# Communication.net
KiCad netlist of a schematic drawn in Altium Designer
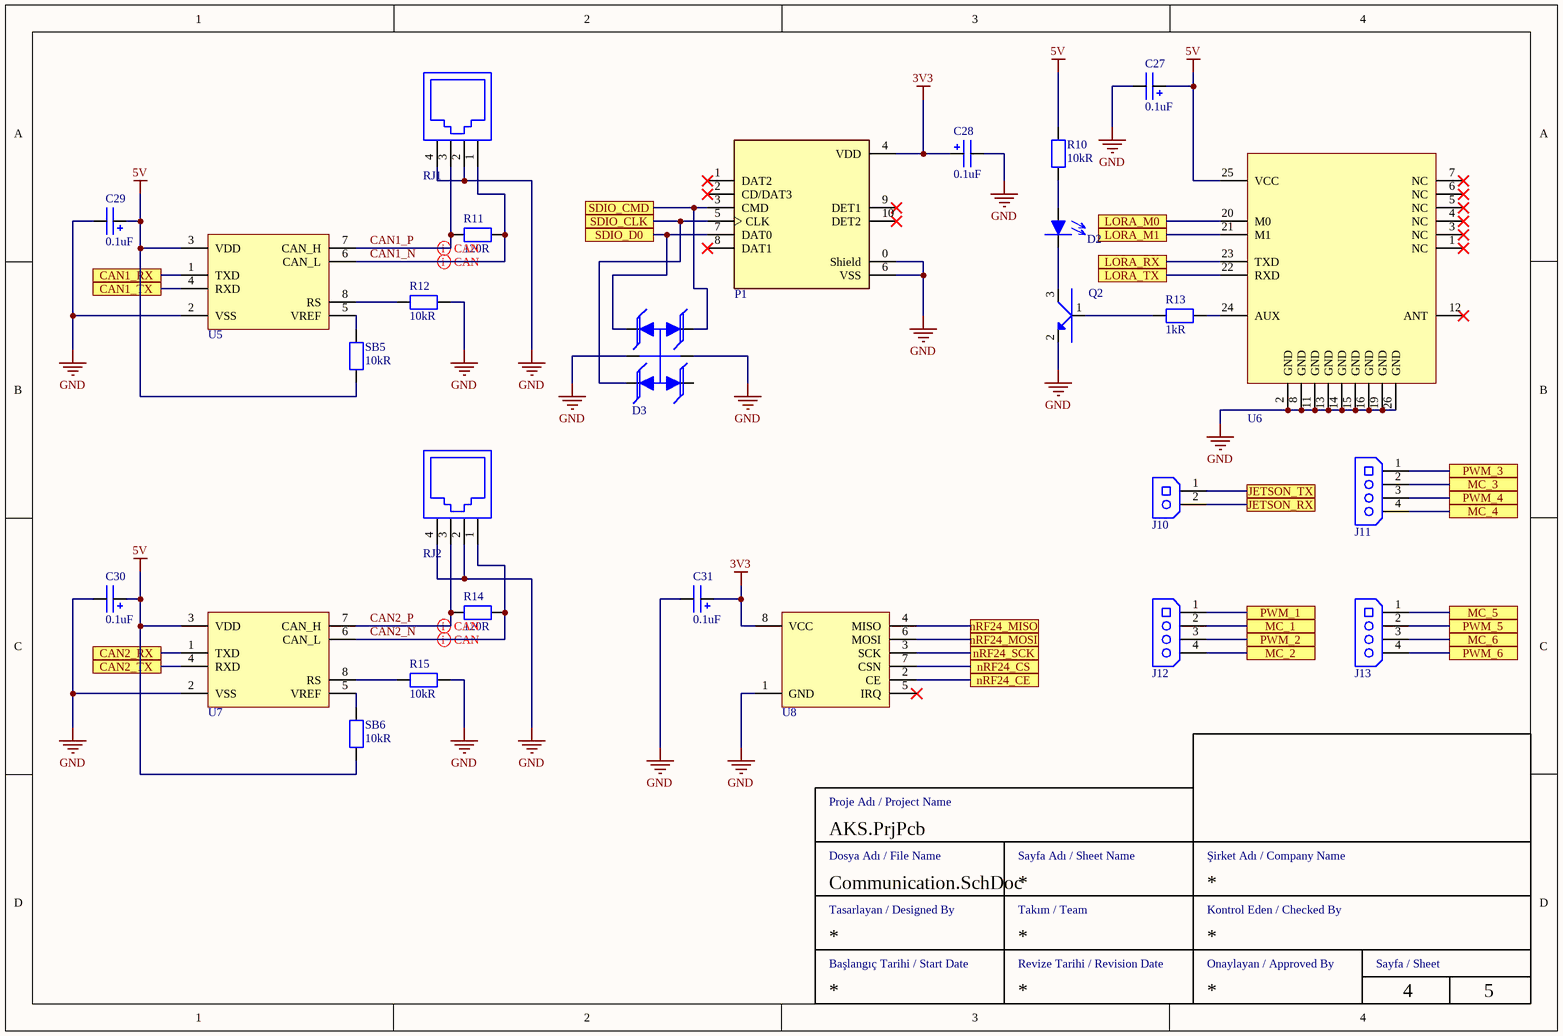
[diagram p0: Communication.SchDoc]

(export (version "E")
  (design (tool "Eeschema 10.0.6"))
  (components
    (comp (ref "C27")
      (value "0.1uF")
      (footprint "CAP 0603")
      (description "Multilayer Ceramic Capacitor")
      (fields (field (name "Comment") "CAP 0603"))
      (libsource (lib "Kaptanyums Lib") (part "CAP 0603"))
    )
    (comp (ref "C28")
      (value "0.1uF")
      (footprint "CAP 0603")
      (description "Multilayer Ceramic Capacitor")
      (fields (field (name "Comment") "CAP 0603"))
      (libsource (lib "Kaptanyums Lib") (part "CAP 0603"))
    )
    (comp (ref "C29")
      (value "0.1uF")
      (footprint "CAP 0603")
      (description "Multilayer Ceramic Capacitor")
      (fields (field (name "Comment") "CAP 0603"))
      (libsource (lib "Kaptanyums Lib") (part "CAP 0603"))
    )
    (comp (ref "C30")
      (value "0.1uF")
      (footprint "CAP 0603")
      (description "Multilayer Ceramic Capacitor")
      (fields (field (name "Comment") "CAP 0603"))
      (libsource (lib "Kaptanyums Lib") (part "CAP 0603"))
    )
    (comp (ref "C31")
      (value "0.1uF")
      (footprint "CAP 0603")
      (description "Multilayer Ceramic Capacitor")
      (fields (field (name "Comment") "CAP 0603"))
      (libsource (lib "Kaptanyums Lib") (part "CAP 0603"))
    )
    (comp (ref "D2")
      (value "LTW-C191TLA")
      (footprint "LED 0603")
      (description "Chip LED")
      (libsource (lib "Kaptanyums Lib") (part "LED 0603"))
    )
    (comp (ref "D3")
      (value "ESDA6V1SC6")
      (footprint "SOT23-6")
      (description "Diode TVS Array")
      (fields (field (name "VOLTAGE") "5.25V"))
      (libsource (lib "Kaptanyums Lib") (part "ESDA6V1SC6"))
    )
    (comp (ref "J10")
      (value "JSTXH2")
      (footprint "JSTXH2")
      (description "JST Socket for PCB")
      (libsource (lib "Kaptanyums Lib") (part "JSTXH2"))
    )
    (comp (ref "J11")
      (value "JSTXH4")
      (footprint "JSTXH4")
      (description "JST Socket for PCB")
      (libsource (lib "Kaptanyums Lib") (part "JSTXH4"))
    )
    (comp (ref "J12")
      (value "JSTXH4")
      (footprint "JSTXH4")
      (description "JST Socket for PCB")
      (libsource (lib "Kaptanyums Lib") (part "JSTXH4"))
    )
    (comp (ref "J13")
      (value "JSTXH4")
      (footprint "JSTXH4")
      (description "JST Socket for PCB")
      (libsource (lib "Kaptanyums Lib") (part "JSTXH4"))
    )
    (comp (ref "P1")
      (value "DM3AT-SF-PEJM5")
      (footprint "SD CARD (8+2)")
      (description "Micro SD Card Adapter")
      (libsource (lib "Kaptanyums Lib") (part "DM3AT-SF-PEJM5"))
    )
    (comp (ref "Q2")
      (value "BC817-40")
      (footprint "SOT23-3")
      (description "Transistor BJT")
      (fields (field (name "VOLTAGE") "45V"))
      (libsource (lib "Kaptanyums Lib") (part "BC817-40"))
    )
    (comp (ref "R10")
      (value "10kR")
      (footprint "RESISTOR 0603")
      (description "SMD Chip Resistor")
      (fields (field (name "Comment") "RES 0603"))
      (libsource (lib "Kaptanyums Lib") (part "RES 0603"))
    )
    (comp (ref "R11")
      (value "120R")
      (footprint "RESISTOR 0603")
      (description "SMD Chip Resistor")
      (fields (field (name "Comment") "RES 0603"))
      (libsource (lib "Kaptanyums Lib") (part "RES 0603"))
    )
    (comp (ref "R12")
      (value "10kR")
      (footprint "RESISTOR 0603")
      (description "SMD Chip Resistor")
      (fields (field (name "Comment") "RES 0603"))
      (libsource (lib "Kaptanyums Lib") (part "RES 0603"))
    )
    (comp (ref "R13")
      (value "1kR")
      (footprint "RESISTOR 0603")
      (description "SMD Chip Resistor")
      (fields (field (name "Comment") "RES 0603"))
      (libsource (lib "Kaptanyums Lib") (part "RES 0603"))
    )
    (comp (ref "R14")
      (value "120R")
      (footprint "RESISTOR 0603")
      (description "SMD Chip Resistor")
      (fields (field (name "Comment") "RES 0603"))
      (libsource (lib "Kaptanyums Lib") (part "RES 0603"))
    )
    (comp (ref "R15")
      (value "10kR")
      (footprint "RESISTOR 0603")
      (description "SMD Chip Resistor")
      (fields (field (name "Comment") "RES 0603"))
      (libsource (lib "Kaptanyums Lib") (part "RES 0603"))
    )
    (comp (ref "RJ1")
      (value "DS1133-03-S60BX")
      (footprint "RJ6P4C")
      (description "RJ11 Jack")
      (libsource (lib "Kaptanyums Lib") (part "RJ11"))
    )
    (comp (ref "RJ2")
      (value "DS1133-03-S60BX")
      (footprint "RJ6P4C")
      (description "RJ11 Jack")
      (libsource (lib "Kaptanyums Lib") (part "RJ11"))
    )
    (comp (ref "SB5")
      (value "10kR")
      (footprint "RESISTOR 0603")
      (description "SMD Chip Resistor")
      (fields (field (name "Comment") "RES 0603"))
      (libsource (lib "Kaptanyums Lib") (part "RES 0603"))
    )
    (comp (ref "SB6")
      (value "10kR")
      (footprint "RESISTOR 0603")
      (description "SMD Chip Resistor")
      (fields (field (name "Comment") "RES 0603"))
      (libsource (lib "Kaptanyums Lib") (part "RES 0603"))
    )
    (comp (ref "U5")
      (value "MCP2551T-I")
      (footprint "SOIC-8")
      (description "CAN Transceiver")
      (libsource (lib "Kaptanyums Lib") (part "MCP2551T-I"))
    )
    (comp (ref "U6")
      (value "E220-400")
      (footprint "E220-400T22S")
      (description "RF Transceiver")
      (libsource (lib "Kaptanyums Lib") (part "E220-400"))
    )
    (comp (ref "U7")
      (value "MCP2551T-I")
      (footprint "SOIC-8")
      (description "CAN Transceiver")
      (libsource (lib "Kaptanyums Lib") (part "MCP2551T-I"))
    )
    (comp (ref "U8")
      (value "NRF24")
      (footprint "nRF24L01+")
      (description "RF Transceiver")
      (libsource (lib "Kaptanyums Lib") (part "NRF24"))
    )
  )
  (nets
    (net (code "1") (name "/CAN1_N") (class "Default")
      (node (ref "R11") (pin "1") (pinfunction "1_1") (pintype "passive"))
      (node (ref "RJ1") (pin "1") (pinfunction "1_1") (pintype "passive"))
      (node (ref "U5") (pin "6") (pinfunction "CAN_L_6") (pintype "passive"))
    )
    (net (code "2") (name "/CAN1_P") (class "Default")
      (node (ref "R11") (pin "2") (pinfunction "2_2") (pintype "passive"))
      (node (ref "RJ1") (pin "3") (pinfunction "3_3") (pintype "passive"))
      (node (ref "U5") (pin "7") (pinfunction "CAN_H_7") (pintype "passive"))
    )
    (net (code "3") (name "/CAN1_RX") (class "Default")
      (node (ref "U5") (pin "1") (pinfunction "TXD_1") (pintype "passive"))
    )
    (net (code "4") (name "/CAN1_TX") (class "Default")
      (node (ref "U5") (pin "4") (pinfunction "RXD_4") (pintype "passive"))
    )
    (net (code "5") (name "/CAN2_N") (class "Default")
      (node (ref "R14") (pin "1") (pinfunction "1_1") (pintype "passive"))
      (node (ref "RJ2") (pin "1") (pinfunction "1_1") (pintype "passive"))
      (node (ref "U7") (pin "6") (pinfunction "CAN_L_6") (pintype "passive"))
    )
    (net (code "6") (name "/CAN2_P") (class "Default")
      (node (ref "R14") (pin "2") (pinfunction "2_2") (pintype "passive"))
      (node (ref "RJ2") (pin "3") (pinfunction "3_3") (pintype "passive"))
      (node (ref "U7") (pin "7") (pinfunction "CAN_H_7") (pintype "passive"))
    )
    (net (code "7") (name "/CAN2_RX") (class "Default")
      (node (ref "U7") (pin "1") (pinfunction "TXD_1") (pintype "passive"))
    )
    (net (code "8") (name "/CAN2_TX") (class "Default")
      (node (ref "U7") (pin "4") (pinfunction "RXD_4") (pintype "passive"))
    )
    (net (code "9") (name "/JETSON_RX") (class "Default")
      (node (ref "J10") (pin "2") (pinfunction "2_2") (pintype "passive"))
    )
    (net (code "10") (name "/JETSON_TX") (class "Default")
      (node (ref "J10") (pin "1") (pinfunction "1_1") (pintype "passive"))
    )
    (net (code "11") (name "/LORA_M0") (class "Default")
      (node (ref "U6") (pin "20") (pinfunction "M0_20") (pintype "passive"))
    )
    (net (code "12") (name "/LORA_M1") (class "Default")
      (node (ref "U6") (pin "21") (pinfunction "M1_21") (pintype "passive"))
    )
    (net (code "13") (name "/LORA_RX") (class "Default")
      (node (ref "U6") (pin "23") (pinfunction "TXD_23") (pintype "passive"))
    )
    (net (code "14") (name "/LORA_TX") (class "Default")
      (node (ref "U6") (pin "22") (pinfunction "RXD_22") (pintype "passive"))
    )
    (net (code "15") (name "/MC_1") (class "Default")
      (node (ref "J12") (pin "2") (pinfunction "2_2") (pintype "passive"))
    )
    (net (code "16") (name "/MC_2") (class "Default")
      (node (ref "J12") (pin "4") (pinfunction "4_4") (pintype "passive"))
    )
    (net (code "17") (name "/MC_3") (class "Default")
      (node (ref "J11") (pin "2") (pinfunction "2_2") (pintype "passive"))
    )
    (net (code "18") (name "/MC_4") (class "Default")
      (node (ref "J11") (pin "4") (pinfunction "4_4") (pintype "passive"))
    )
    (net (code "19") (name "/MC_5") (class "Default")
      (node (ref "J13") (pin "1") (pinfunction "1_1") (pintype "passive"))
    )
    (net (code "20") (name "/MC_6") (class "Default")
      (node (ref "J13") (pin "3") (pinfunction "3_3") (pintype "passive"))
    )
    (net (code "21") (name "/PWM_1") (class "Default")
      (node (ref "J12") (pin "1") (pinfunction "1_1") (pintype "passive"))
    )
    (net (code "22") (name "/PWM_2") (class "Default")
      (node (ref "J12") (pin "3") (pinfunction "3_3") (pintype "passive"))
    )
    (net (code "23") (name "/PWM_3") (class "Default")
      (node (ref "J11") (pin "1") (pinfunction "1_1") (pintype "passive"))
    )
    (net (code "24") (name "/PWM_4") (class "Default")
      (node (ref "J11") (pin "3") (pinfunction "3_3") (pintype "passive"))
    )
    (net (code "25") (name "/PWM_5") (class "Default")
      (node (ref "J13") (pin "2") (pinfunction "2_2") (pintype "passive"))
    )
    (net (code "26") (name "/PWM_6") (class "Default")
      (node (ref "J13") (pin "4") (pinfunction "4_4") (pintype "passive"))
    )
    (net (code "27") (name "/SDIO_CLK") (class "Default")
      (node (ref "D3") (pin "6") (pinfunction "6_6") (pintype "passive"))
      (node (ref "P1") (pin "5") (pinfunction "CLK_5") (pintype "passive"))
    )
    (net (code "28") (name "/SDIO_CMD") (class "Default")
      (node (ref "D3") (pin "3") (pinfunction "3_3") (pintype "passive"))
      (node (ref "P1") (pin "3") (pinfunction "CMD_3") (pintype "passive"))
    )
    (net (code "29") (name "/SDIO_D0") (class "Default")
      (node (ref "D3") (pin "4") (pinfunction "4_4") (pintype "passive"))
      (node (ref "P1") (pin "7") (pinfunction "DAT0_7") (pintype "passive"))
    )
    (net (code "30") (name "/nRF24_CE") (class "Default")
      (node (ref "U8") (pin "2") (pinfunction "CE_2") (pintype "passive"))
    )
    (net (code "31") (name "/nRF24_CS") (class "Default")
      (node (ref "U8") (pin "7") (pinfunction "CSN_7") (pintype "passive"))
    )
    (net (code "32") (name "/nRF24_MISO") (class "Default")
      (node (ref "U8") (pin "4") (pinfunction "MISO_4") (pintype "passive"))
    )
    (net (code "33") (name "/nRF24_MOSI") (class "Default")
      (node (ref "U8") (pin "6") (pinfunction "MOSI_6") (pintype "passive"))
    )
    (net (code "34") (name "/nRF24_SCK") (class "Default")
      (node (ref "U8") (pin "3") (pinfunction "SCK_3") (pintype "passive"))
    )
    (net (code "35") (name "3V3") (class "Default")
      (node (ref "C28") (pin "1") (pinfunction "1_1") (pintype "passive"))
      (node (ref "C31") (pin "1") (pinfunction "1_1") (pintype "passive"))
      (node (ref "P1") (pin "4") (pinfunction "VDD_4") (pintype "power_in"))
      (node (ref "U8") (pin "8") (pinfunction "VCC_8") (pintype "passive"))
    )
    (net (code "36") (name "5V") (class "Default")
      (node (ref "C27") (pin "1") (pinfunction "1_1") (pintype "passive"))
      (node (ref "C29") (pin "1") (pinfunction "1_1") (pintype "passive"))
      (node (ref "C30") (pin "1") (pinfunction "1_1") (pintype "passive"))
      (node (ref "R10") (pin "2") (pinfunction "2_2") (pintype "passive"))
      (node (ref "SB5") (pin "1") (pinfunction "1_1") (pintype "passive"))
      (node (ref "SB6") (pin "1") (pinfunction "1_1") (pintype "passive"))
      (node (ref "U5") (pin "3") (pinfunction "VDD_3") (pintype "passive"))
      (node (ref "U6") (pin "25") (pinfunction "VCC_25") (pintype "passive"))
      (node (ref "U7") (pin "3") (pinfunction "VDD_3") (pintype "passive"))
    )
    (net (code "37") (name "GND") (class "Default")
      (node (ref "C27") (pin "2") (pinfunction "2_2") (pintype "passive"))
      (node (ref "C28") (pin "2") (pinfunction "2_2") (pintype "passive"))
      (node (ref "C29") (pin "2") (pinfunction "2_2") (pintype "passive"))
      (node (ref "C30") (pin "2") (pinfunction "2_2") (pintype "passive"))
      (node (ref "C31") (pin "2") (pinfunction "2_2") (pintype "passive"))
      (node (ref "D3") (pin "2") (pinfunction "2_2") (pintype "passive"))
      (node (ref "D3") (pin "5") (pinfunction "5_5") (pintype "passive"))
      (node (ref "P1") (pin "0") (pinfunction "Shield_0") (pintype "passive"))
      (node (ref "P1") (pin "6") (pinfunction "VSS_6") (pintype "power_in"))
      (node (ref "Q2") (pin "2") (pinfunction "S_2") (pintype "passive"))
      (node (ref "R12") (pin "2") (pinfunction "2_2") (pintype "passive"))
      (node (ref "R15") (pin "2") (pinfunction "2_2") (pintype "passive"))
      (node (ref "RJ1") (pin "2") (pinfunction "2_2") (pintype "passive"))
      (node (ref "RJ1") (pin "4") (pinfunction "4_4") (pintype "passive"))
      (node (ref "RJ2") (pin "2") (pinfunction "2_2") (pintype "passive"))
      (node (ref "RJ2") (pin "4") (pinfunction "4_4") (pintype "passive"))
      (node (ref "U5") (pin "2") (pinfunction "VSS_2") (pintype "passive"))
      (node (ref "U6") (pin "11") (pinfunction "GND_11") (pintype "passive"))
      (node (ref "U6") (pin "13") (pinfunction "GND_13") (pintype "passive"))
      (node (ref "U6") (pin "14") (pinfunction "GND_14") (pintype "passive"))
      (node (ref "U6") (pin "15") (pinfunction "GND_15") (pintype "passive"))
      (node (ref "U6") (pin "16") (pinfunction "GND_16") (pintype "passive"))
      (node (ref "U6") (pin "19") (pinfunction "GND_19") (pintype "passive"))
      (node (ref "U6") (pin "2") (pinfunction "GND_2") (pintype "passive"))
      (node (ref "U6") (pin "26") (pinfunction "GND_26") (pintype "passive"))
      (node (ref "U6") (pin "8") (pinfunction "GND_8") (pintype "passive"))
      (node (ref "U7") (pin "2") (pinfunction "VSS_2") (pintype "passive"))
      (node (ref "U8") (pin "1") (pinfunction "GND_1") (pintype "passive"))
    )
    (net (code "38") (name "Net-(D2-Pad2)") (class "Default")
      (node (ref "D2") (pin "2") (pinfunction "2_2") (pintype "passive"))
      (node (ref "R10") (pin "1") (pinfunction "1_1") (pintype "passive"))
    )
    (net (code "39") (name "Net-(Q2-D)") (class "Default")
      (node (ref "D2") (pin "1") (pinfunction "1_1") (pintype "passive"))
      (node (ref "Q2") (pin "3") (pinfunction "D_3") (pintype "passive"))
    )
    (net (code "40") (name "Net-(Q2-G)") (class "Default")
      (node (ref "Q2") (pin "1") (pinfunction "G_1") (pintype "passive"))
      (node (ref "R13") (pin "1") (pinfunction "1_1") (pintype "passive"))
    )
    (net (code "41") (name "Net-(U5-RS)") (class "Default")
      (node (ref "R12") (pin "1") (pinfunction "1_1") (pintype "passive"))
      (node (ref "U5") (pin "8") (pinfunction "RS_8") (pintype "passive"))
    )
    (net (code "42") (name "Net-(U5-VREF)") (class "Default")
      (node (ref "SB5") (pin "2") (pinfunction "2_2") (pintype "passive"))
      (node (ref "U5") (pin "5") (pinfunction "VREF_5") (pintype "passive"))
    )
    (net (code "43") (name "Net-(U6-AUX)") (class "Default")
      (node (ref "R13") (pin "2") (pinfunction "2_2") (pintype "passive"))
      (node (ref "U6") (pin "24") (pinfunction "AUX_24") (pintype "passive"))
    )
    (net (code "44") (name "Net-(U7-RS)") (class "Default")
      (node (ref "R15") (pin "1") (pinfunction "1_1") (pintype "passive"))
      (node (ref "U7") (pin "8") (pinfunction "RS_8") (pintype "passive"))
    )
    (net (code "45") (name "Net-(U7-VREF)") (class "Default")
      (node (ref "SB6") (pin "2") (pinfunction "2_2") (pintype "passive"))
      (node (ref "U7") (pin "5") (pinfunction "VREF_5") (pintype "passive"))
    )
    (net (code "46") (name "unconnected-(D3-Pad1)") (class "Default")
      (node (ref "D3") (pin "1") (pinfunction "1_1") (pintype "passive"))
    )
    (net (code "47") (name "unconnected-(P1-CD{slash}DAT3-Pad2)") (class "Default")
      (node (ref "P1") (pin "2") (pinfunction "CD/DAT3_2") (pintype "passive+no_connect"))
    )
    (net (code "48") (name "unconnected-(P1-DAT1-Pad8)") (class "Default")
      (node (ref "P1") (pin "8") (pinfunction "DAT1_8") (pintype "passive+no_connect"))
    )
    (net (code "49") (name "unconnected-(P1-DAT2-Pad1)") (class "Default")
      (node (ref "P1") (pin "1") (pinfunction "DAT2_1") (pintype "passive+no_connect"))
    )
    (net (code "50") (name "unconnected-(P1-DET1-Pad9)") (class "Default")
      (node (ref "P1") (pin "9") (pinfunction "DET1_9") (pintype "passive+no_connect"))
    )
    (net (code "51") (name "unconnected-(P1-DET2-Pad10)") (class "Default")
      (node (ref "P1") (pin "10") (pinfunction "DET2_10") (pintype "passive+no_connect"))
    )
    (net (code "52") (name "unconnected-(U6-ANT-Pad12)") (class "Default")
      (node (ref "U6") (pin "12") (pinfunction "ANT_12") (pintype "passive+no_connect"))
    )
    (net (code "53") (name "unconnected-(U6-NC-Pad1)") (class "Default")
      (node (ref "U6") (pin "1") (pinfunction "NC_1") (pintype "passive+no_connect"))
    )
    (net (code "54") (name "unconnected-(U6-NC-Pad3)") (class "Default")
      (node (ref "U6") (pin "3") (pinfunction "NC_3") (pintype "passive+no_connect"))
    )
    (net (code "55") (name "unconnected-(U6-NC-Pad4)") (class "Default")
      (node (ref "U6") (pin "4") (pinfunction "NC_4") (pintype "passive+no_connect"))
    )
    (net (code "56") (name "unconnected-(U6-NC-Pad5)") (class "Default")
      (node (ref "U6") (pin "5") (pinfunction "NC_5") (pintype "passive+no_connect"))
    )
    (net (code "57") (name "unconnected-(U6-NC-Pad6)") (class "Default")
      (node (ref "U6") (pin "6") (pinfunction "NC_6") (pintype "passive+no_connect"))
    )
    (net (code "58") (name "unconnected-(U6-NC-Pad7)") (class "Default")
      (node (ref "U6") (pin "7") (pinfunction "NC_7") (pintype "passive+no_connect"))
    )
    (net (code "59") (name "unconnected-(U8-IRQ-Pad5)") (class "Default")
      (node (ref "U8") (pin "5") (pinfunction "IRQ_5") (pintype "passive+no_connect"))
    )
  )
)
